# pc_healthypi_move_finger_sensor_v1.net
KiCad netlist of a schematic drawn in EAGLE
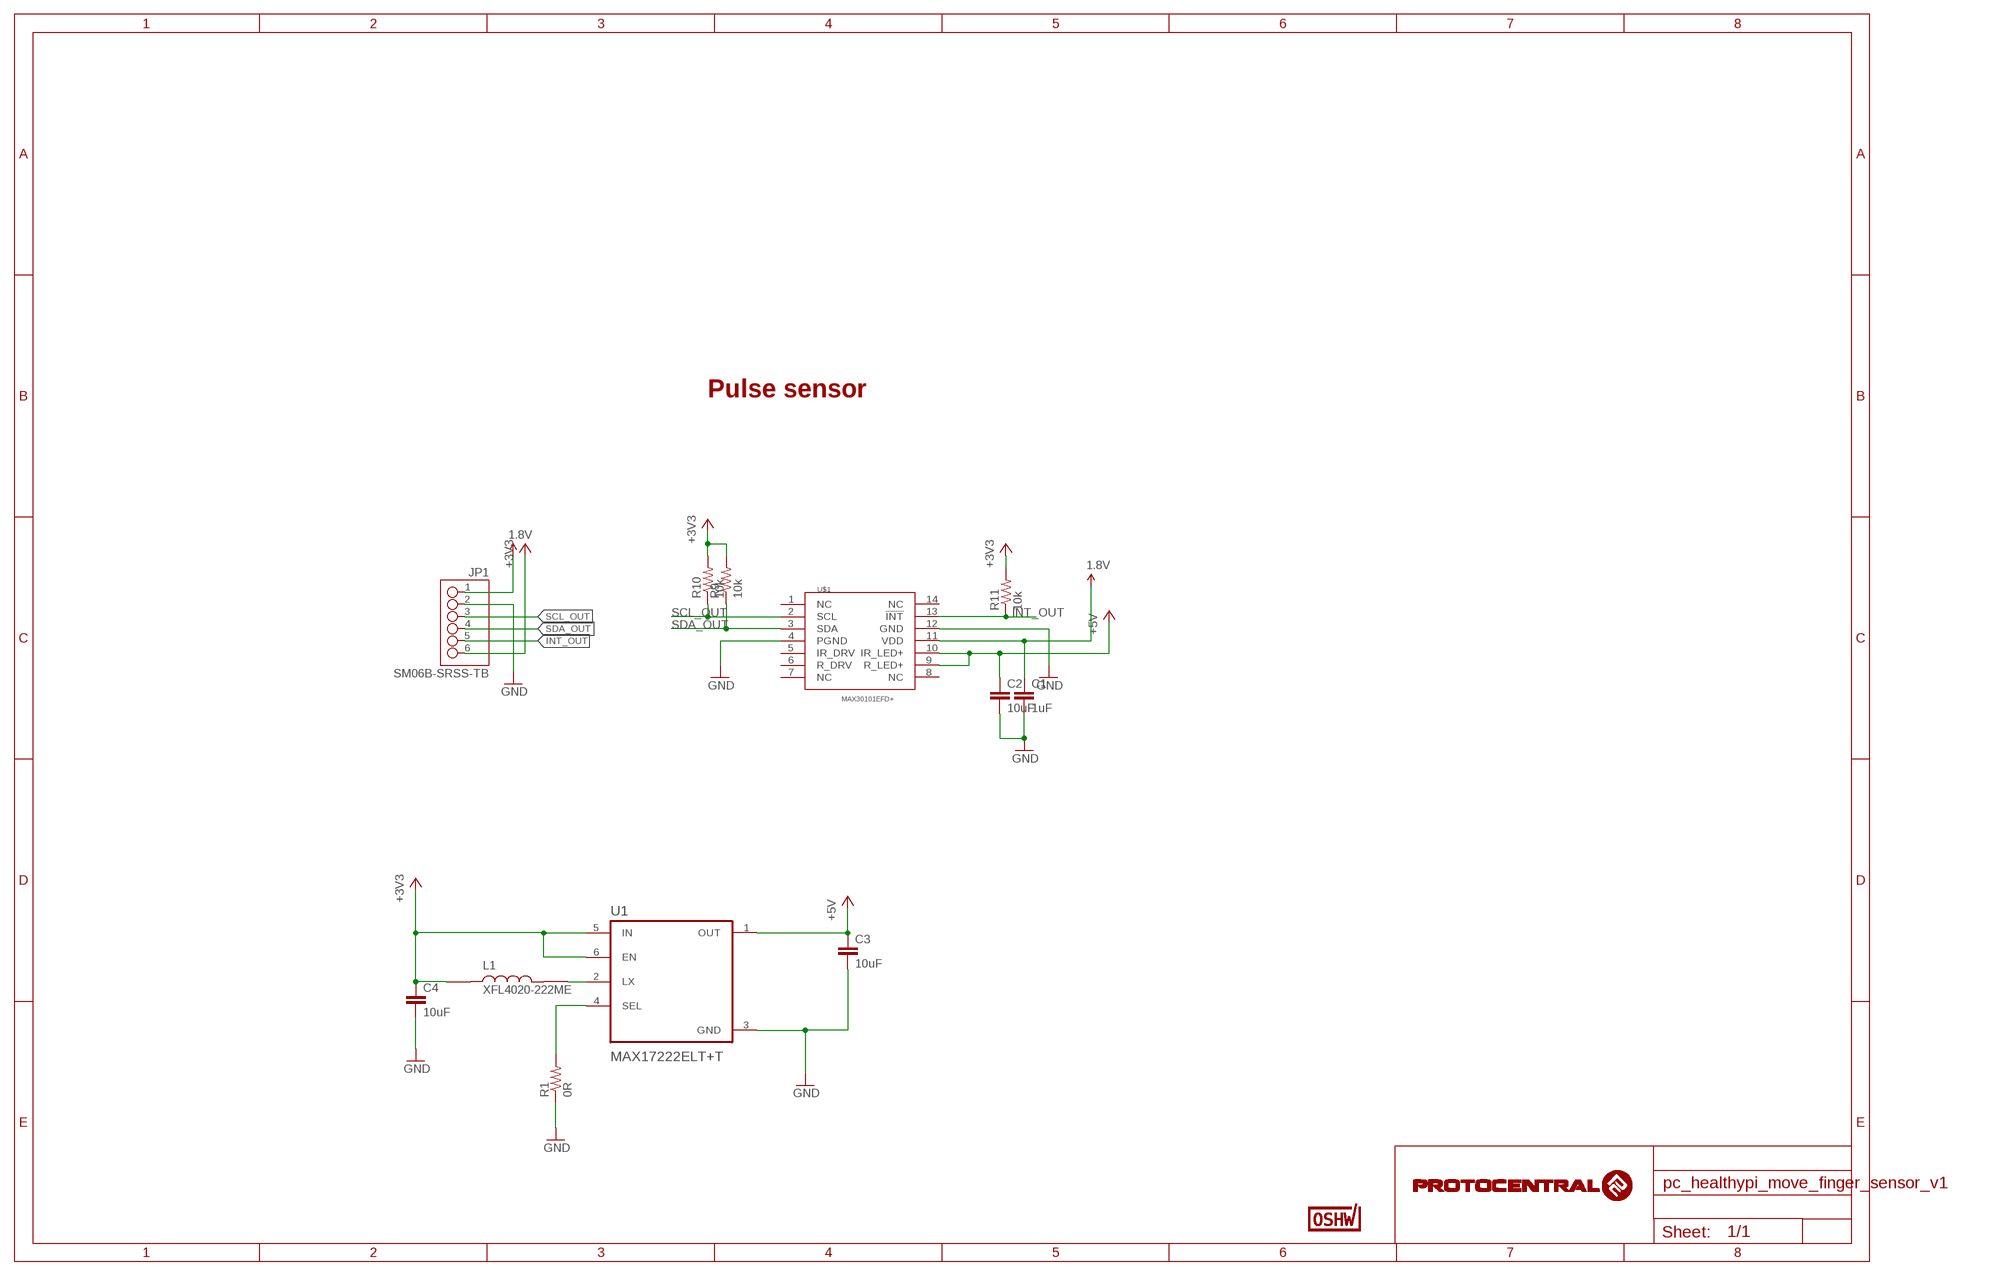
[diagram p0: schematic, sheet 1]

(export (version "E")
  (design (tool "Eeschema 10.0.6"))
  (components
    (comp (ref "C1")
      (value "1uF")
      (footprint "eagle-import:C0402")
      (libsource (lib "eagle-import") (part "C-EUC0402"))
    )
    (comp (ref "C2")
      (value "10uF")
      (footprint "eagle-import:C0402")
      (libsource (lib "eagle-import") (part "C-EUC0402"))
    )
    (comp (ref "C3")
      (value "10uF")
      (footprint "eagle-import:C0402")
      (libsource (lib "eagle-import") (part "C-EUC0402"))
    )
    (comp (ref "C4")
      (value "10uF")
      (footprint "eagle-import:C0402")
      (libsource (lib "eagle-import") (part "C-EUC0402"))
    )
    (comp (ref "JP1")
      (value "SM06B-SRSS-TB")
      (footprint "eagle-import:SM06B-SRSS-TB")
      (fields (field (name "MF") "JST Sales"))
      (libsource (lib "eagle-import") (part "SM06B-SRSS-TB"))
    )
    (comp (ref "L1")
      (value "XFL4020-222ME")
      (footprint "eagle-import:IND_XFL4020-222ME")
      (fields (field (name "MF") "Coilcraft"))
      (libsource (lib "eagle-import") (part "XFL4020-222ME"))
    )
    (comp (ref "R1")
      (value "0R")
      (footprint "eagle-import:R0402")
      (libsource (lib "eagle-import") (part "R-US_R0402"))
    )
    (comp (ref "R9")
      (value "10k")
      (footprint "eagle-import:R0402")
      (libsource (lib "eagle-import") (part "R-US_R0402"))
    )
    (comp (ref "R10")
      (value "10k")
      (footprint "eagle-import:R0402")
      (libsource (lib "eagle-import") (part "R-US_R0402"))
    )
    (comp (ref "R11")
      (value "10k")
      (footprint "eagle-import:R0402")
      (libsource (lib "eagle-import") (part "R-US_R0402"))
    )
    (comp (ref "U$1")
      (value "MAX30101EFD+")
      (footprint "eagle-import:OESIP-14")
      (libsource (lib "eagle-import") (part "MAX30100"))
    )
    (comp (ref "U$9")
      (value "CERT-SMALL")
      (footprint "eagle-import:CERT-SMALL-SILK")
      (libsource (lib "eagle-import") (part "CERT-SMALL"))
    )
    (comp (ref "U1")
      (value "MAX17222ELT+T")
      (footprint "eagle-import:SON65P200X200X80-6N")
      (fields (field (name "MF") "Analog Devices"))
      (libsource (lib "eagle-import") (part "MAX17222ELT+T"))
    )
  )
  (nets
    (net (code "1") (name "+3V3") (class "Default")
      (node (ref "C4") (pin "1") (pinfunction "1_1") (pintype "passive"))
      (node (ref "JP1") (pin "6") (pinfunction "P$6_6") (pintype "bidirectional"))
      (node (ref "L1") (pin "1") (pinfunction "1_1") (pintype "passive"))
      (node (ref "R10") (pin "2") (pinfunction "2_2") (pintype "passive"))
      (node (ref "R11") (pin "2") (pinfunction "2_2") (pintype "passive"))
      (node (ref "R9") (pin "2") (pinfunction "2_2") (pintype "passive"))
      (node (ref "U1") (pin "5") (pinfunction "IN_5") (pintype "input"))
      (node (ref "U1") (pin "6") (pinfunction "EN_6") (pintype "bidirectional"))
    )
    (net (code "2") (name "+5V") (class "Default")
      (node (ref "C2") (pin "1") (pinfunction "1_1") (pintype "passive"))
      (node (ref "C3") (pin "1") (pinfunction "1_1") (pintype "passive"))
      (node (ref "U$1") (pin "10") (pinfunction "IR_LED+_10") (pintype "bidirectional"))
      (node (ref "U$1") (pin "9") (pinfunction "R_LED+_9") (pintype "bidirectional"))
      (node (ref "U1") (pin "1") (pinfunction "OUT_1") (pintype "output"))
    )
    (net (code "3") (name "1.8V") (class "Default")
      (node (ref "C1") (pin "1") (pinfunction "1_1") (pintype "passive"))
      (node (ref "JP1") (pin "1") (pinfunction "P$1_1") (pintype "bidirectional"))
      (node (ref "U$1") (pin "11") (pinfunction "VDD_11") (pintype "bidirectional"))
    )
    (net (code "4") (name "GND") (class "Default")
      (node (ref "C1") (pin "2") (pinfunction "2_2") (pintype "passive"))
      (node (ref "C2") (pin "2") (pinfunction "2_2") (pintype "passive"))
      (node (ref "C3") (pin "2") (pinfunction "2_2") (pintype "passive"))
      (node (ref "C4") (pin "2") (pinfunction "2_2") (pintype "passive"))
      (node (ref "JP1") (pin "2") (pinfunction "P$2_2") (pintype "bidirectional"))
      (node (ref "R1") (pin "1") (pinfunction "1_1") (pintype "passive"))
      (node (ref "U$1") (pin "12") (pinfunction "GND_12") (pintype "bidirectional"))
      (node (ref "U$1") (pin "4") (pinfunction "PGND_4") (pintype "bidirectional"))
      (node (ref "U1") (pin "3") (pinfunction "GND_3") (pintype "power_in"))
    )
    (net (code "5") (name "INT_OUT") (class "Default")
      (node (ref "JP1") (pin "5") (pinfunction "P$5_5") (pintype "bidirectional"))
      (node (ref "R11") (pin "1") (pinfunction "1_1") (pintype "passive"))
      (node (ref "U$1") (pin "13") (pinfunction "~{INT}_13") (pintype "bidirectional"))
    )
    (net (code "6") (name "Net-(U1-LX)") (class "Default")
      (node (ref "L1") (pin "2") (pinfunction "2_2") (pintype "passive"))
      (node (ref "U1") (pin "2") (pinfunction "LX_2") (pintype "bidirectional"))
    )
    (net (code "7") (name "Net-(U1-SEL)") (class "Default")
      (node (ref "R1") (pin "2") (pinfunction "2_2") (pintype "passive"))
      (node (ref "U1") (pin "4") (pinfunction "SEL_4") (pintype "bidirectional"))
    )
    (net (code "8") (name "SCL_OUT") (class "Default")
      (node (ref "JP1") (pin "3") (pinfunction "P$3_3") (pintype "bidirectional"))
      (node (ref "R10") (pin "1") (pinfunction "1_1") (pintype "passive"))
      (node (ref "U$1") (pin "2") (pinfunction "SCL_2") (pintype "bidirectional"))
    )
    (net (code "9") (name "SDA_OUT") (class "Default")
      (node (ref "JP1") (pin "4") (pinfunction "P$4_4") (pintype "bidirectional"))
      (node (ref "R9") (pin "1") (pinfunction "1_1") (pintype "passive"))
      (node (ref "U$1") (pin "3") (pinfunction "SDA_3") (pintype "bidirectional"))
    )
    (net (code "10") (name "unconnected-(U$1-IR_DRV-Pad5)") (class "Default")
      (node (ref "U$1") (pin "5") (pinfunction "IR_DRV_5") (pintype "bidirectional"))
    )
    (net (code "11") (name "unconnected-(U$1-NC-Pad1)") (class "Default")
      (node (ref "U$1") (pin "1") (pinfunction "NC_1") (pintype "bidirectional"))
    )
    (net (code "12") (name "unconnected-(U$1-NC-Pad7)") (class "Default")
      (node (ref "U$1") (pin "7") (pinfunction "NC_7") (pintype "bidirectional"))
    )
    (net (code "13") (name "unconnected-(U$1-NC-Pad8)") (class "Default")
      (node (ref "U$1") (pin "8") (pinfunction "NC_8") (pintype "bidirectional"))
    )
    (net (code "14") (name "unconnected-(U$1-NC-Pad14)") (class "Default")
      (node (ref "U$1") (pin "14") (pinfunction "NC_14") (pintype "bidirectional"))
    )
    (net (code "15") (name "unconnected-(U$1-R_DRV-Pad6)") (class "Default")
      (node (ref "U$1") (pin "6") (pinfunction "R_DRV_6") (pintype "bidirectional"))
    )
  )
)
